# ToneControl.net
KiCad netlist of a schematic drawn in Altium Designer
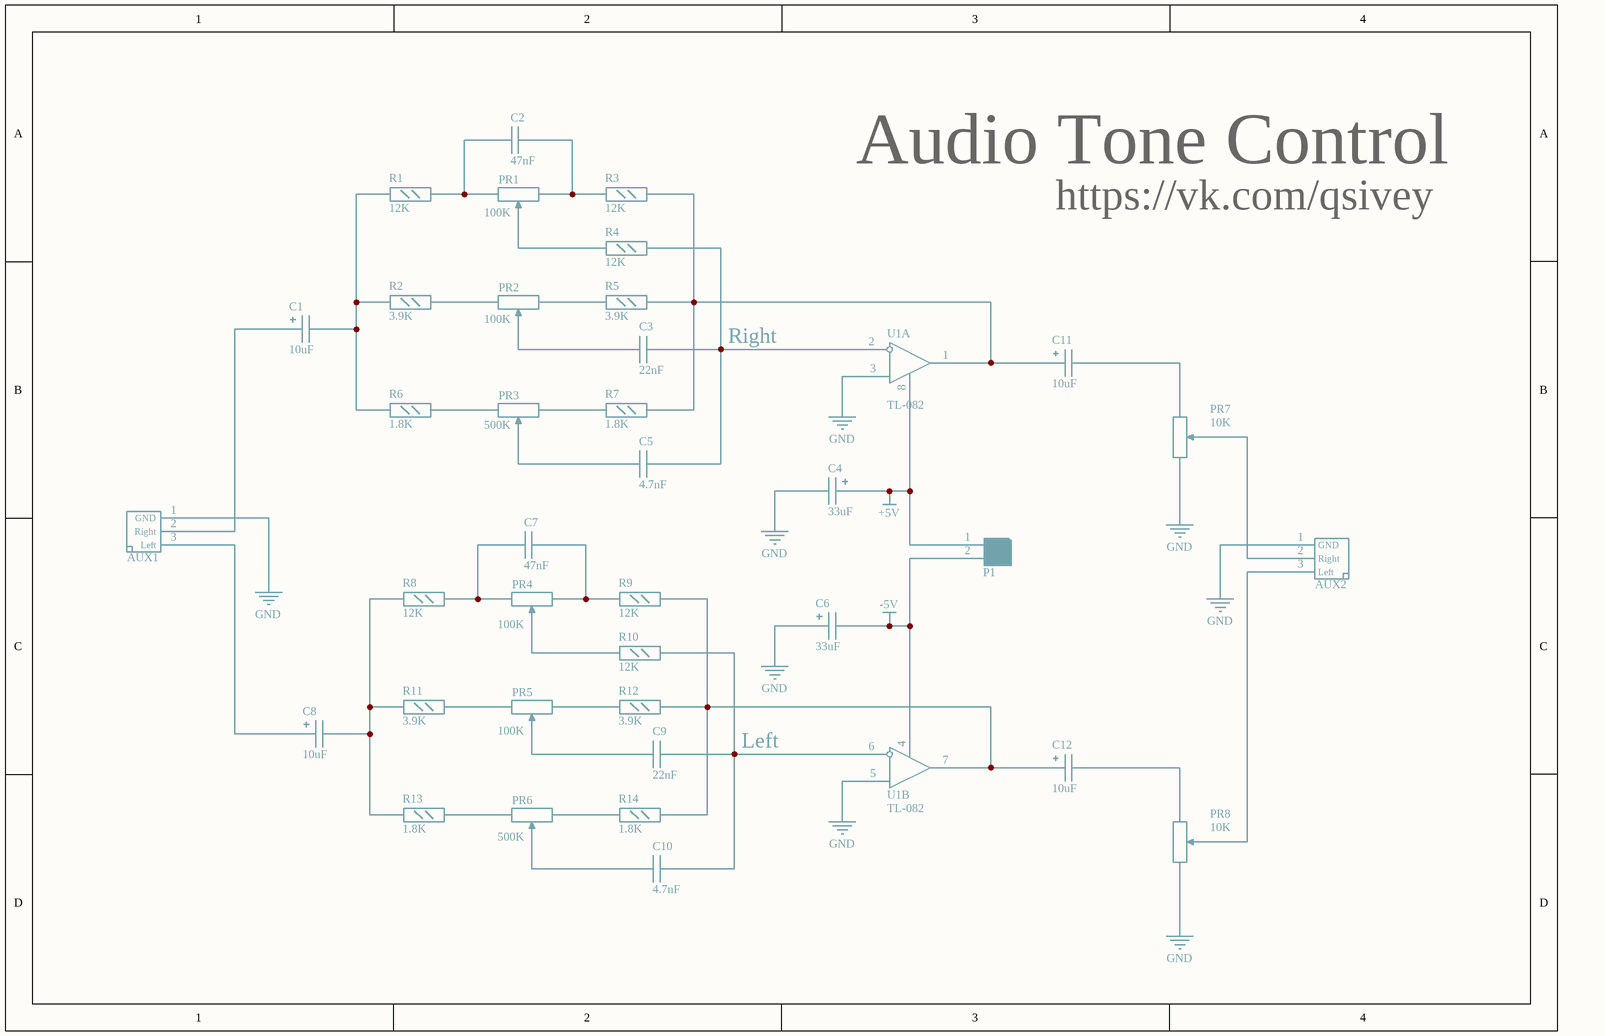
[diagram p0: ToneControl.SchDoc]

(export (version "E")
  (design (tool "Eeschema 10.0.6"))
  (components
    (comp (ref "AUX1") (value "AUX") (footprint "AUX_2") (libsource (lib "") (part "AUX_1")))
    (comp (ref "AUX2") (value "AUX") (footprint "AUX_2") (libsource (lib "CustomMillLib") (part "AUX")))
    (comp (ref "C1")
      (value "10uF")
      (footprint "CAP_POL_MED")
      (libsource (lib "CustomMillLib") (part "Cap_Pol"))
    )
    (comp (ref "C2")
      (value "47nF")
      (footprint "CAP_CER_MED")
      (libsource (lib "CustomMillLib") (part "Cap_Ceram"))
    )
    (comp (ref "C3")
      (value "22nF")
      (footprint "CAP_CER_MED")
      (libsource (lib "CustomMillLib") (part "Cap_Ceram"))
    )
    (comp (ref "C4")
      (value "33uF")
      (footprint "CAP_POL_MED")
      (libsource (lib "CustomMillLib") (part "Cap_Pol"))
    )
    (comp (ref "C5")
      (value "4.7nF")
      (footprint "CAP_CER_MED")
      (libsource (lib "CustomMillLib") (part "Cap_Ceram"))
    )
    (comp (ref "C6")
      (value "33uF")
      (footprint "CAP_POL_MED")
      (libsource (lib "CustomMillLib") (part "Cap_Pol"))
    )
    (comp (ref "C7")
      (value "47nF")
      (footprint "CAP_CER_MED")
      (libsource (lib "CustomMillLib") (part "Cap_Ceram"))
    )
    (comp (ref "C8")
      (value "10uF")
      (footprint "CAP_POL_MED")
      (libsource (lib "CustomMillLib") (part "Cap_Pol"))
    )
    (comp (ref "C9")
      (value "22nF")
      (footprint "CAP_CER_MED")
      (libsource (lib "CustomMillLib") (part "Cap_Ceram"))
    )
    (comp (ref "C10")
      (value "4.7nF")
      (footprint "CAP_CER_MED")
      (libsource (lib "CustomMillLib") (part "Cap_Ceram"))
    )
    (comp (ref "C11")
      (value "10uF")
      (footprint "CAP_POL_MED")
      (libsource (lib "CustomMillLib") (part "Cap_Pol"))
    )
    (comp (ref "C12")
      (value "10uF")
      (footprint "CAP_POL_MED")
      (libsource (lib "CustomMillLib") (part "Cap_Pol"))
    )
    (comp (ref "P1")
      (value "Header_2")
      (footprint "HEADER2")
      (libsource (lib "CustomMillLib") (part "Header_2"))
    )
    (comp (ref "PR1") (value "100K") (footprint "REOSTAT_CUS") (libsource (lib "") (part "Reostat_1")))
    (comp (ref "PR2") (value "100K") (footprint "REOSTAT_CUS") (libsource (lib "") (part "Reostat_1")))
    (comp (ref "PR3") (value "500K") (footprint "REOSTAT_CUS") (libsource (lib "") (part "Reostat_1")))
    (comp (ref "PR4") (value "100K") (footprint "REOSTAT_CUS") (libsource (lib "") (part "Reostat_1")))
    (comp (ref "PR5") (value "100K") (footprint "REOSTAT_CUS") (libsource (lib "") (part "Reostat_1")))
    (comp (ref "PR6") (value "500K") (footprint "REOSTAT_CUS") (libsource (lib "") (part "Reostat_1")))
    (comp (ref "PR7")
      (value "10K")
      (footprint "REOSTAT_CUS")
      (libsource (lib "CustomMillLib") (part "Reostat"))
    )
    (comp (ref "PR8")
      (value "10K")
      (footprint "REOSTAT_CUS")
      (libsource (lib "CustomMillLib") (part "Reostat"))
    )
    (comp (ref "R1") (value "12K") (footprint "RES_MED") (libsource (lib "CustomMillLib") (part "Res")))
    (comp (ref "R2") (value "3.9K") (footprint "RES_MED") (libsource (lib "CustomMillLib") (part "Res")))
    (comp (ref "R3") (value "12K") (footprint "RES_MED") (libsource (lib "CustomMillLib") (part "Res")))
    (comp (ref "R4") (value "12K") (footprint "RES_MED") (libsource (lib "CustomMillLib") (part "Res")))
    (comp (ref "R5") (value "3.9K") (footprint "RES_MED") (libsource (lib "CustomMillLib") (part "Res")))
    (comp (ref "R6") (value "1.8K") (footprint "RES_MED") (libsource (lib "CustomMillLib") (part "Res")))
    (comp (ref "R7") (value "1.8K") (footprint "RES_MED") (libsource (lib "CustomMillLib") (part "Res")))
    (comp (ref "R8") (value "12K") (footprint "RES_MED") (libsource (lib "CustomMillLib") (part "Res")))
    (comp (ref "R9") (value "12K") (footprint "RES_MED") (libsource (lib "CustomMillLib") (part "Res")))
    (comp (ref "R10") (value "12K") (footprint "RES_MED") (libsource (lib "CustomMillLib") (part "Res")))
    (comp (ref "R11") (value "3.9K") (footprint "RES_MED") (libsource (lib "CustomMillLib") (part "Res")))
    (comp (ref "R12") (value "3.9K") (footprint "RES_MED") (libsource (lib "CustomMillLib") (part "Res")))
    (comp (ref "R13") (value "1.8K") (footprint "RES_MED") (libsource (lib "CustomMillLib") (part "Res")))
    (comp (ref "R14") (value "1.8K") (footprint "RES_MED") (libsource (lib "CustomMillLib") (part "Res")))
    (comp (ref "U1")
      (value "TL-082")
      (footprint "PCBMillLib:DIP8")
      (libsource (lib "CustomMillLib") (part "OpAmp_8"))
    )
  )
  (nets
    (net (code "1") (name "+5V") (class "Default")
      (node (ref "C4") (pin "1") (pinfunction "61_1") (pintype "passive"))
      (node (ref "P1") (pin "1") (pinfunction "1_1") (pintype "passive"))
      (node (ref "U1") (pin "8") (pinfunction "4_8") (pintype "passive"))
    )
    (net (code "2") (name "-5V") (class "Default")
      (node (ref "C6") (pin "2") (pinfunction "62_2") (pintype "passive"))
      (node (ref "P1") (pin "2") (pinfunction "2_2") (pintype "passive"))
      (node (ref "U1") (pin "4") (pinfunction "4_4") (pintype "passive"))
    )
    (net (code "3") (name "GND") (class "Default")
      (node (ref "AUX1") (pin "1") (pinfunction "GND_1") (pintype "passive"))
      (node (ref "AUX2") (pin "1") (pinfunction "GND_1") (pintype "passive"))
      (node (ref "C4") (pin "2") (pinfunction "62_2") (pintype "passive"))
      (node (ref "C6") (pin "1") (pinfunction "61_1") (pintype "passive"))
      (node (ref "PR7") (pin "3") (pinfunction "3_3") (pintype "passive"))
      (node (ref "PR8") (pin "3") (pinfunction "3_3") (pintype "passive"))
      (node (ref "U1") (pin "3") (pinfunction "8_3") (pintype "passive"))
      (node (ref "U1") (pin "5") (pinfunction "8_5") (pintype "passive"))
    )
    (net (code "4") (name "Net-(AUX1-Left)") (class "Default")
      (node (ref "AUX1") (pin "3") (pinfunction "Left_3") (pintype "passive"))
      (node (ref "C8") (pin "1") (pinfunction "61_1") (pintype "passive"))
    )
    (net (code "5") (name "Net-(AUX1-Right)") (class "Default")
      (node (ref "AUX1") (pin "2") (pinfunction "Right_2") (pintype "passive"))
      (node (ref "C1") (pin "1") (pinfunction "61_1") (pintype "passive"))
    )
    (net (code "6") (name "Net-(AUX2-Left)") (class "Default")
      (node (ref "AUX2") (pin "3") (pinfunction "Left_3") (pintype "passive"))
      (node (ref "PR8") (pin "2") (pinfunction "2_2") (pintype "passive"))
    )
    (net (code "7") (name "Net-(AUX2-Right)") (class "Default")
      (node (ref "AUX2") (pin "2") (pinfunction "Right_2") (pintype "passive"))
      (node (ref "PR7") (pin "2") (pinfunction "2_2") (pintype "passive"))
    )
    (net (code "8") (name "Net-(C1-62)") (class "Default")
      (node (ref "C1") (pin "2") (pinfunction "62_2") (pintype "passive"))
      (node (ref "R1") (pin "1") (pinfunction "2_1") (pintype "passive"))
      (node (ref "R2") (pin "1") (pinfunction "2_1") (pintype "passive"))
      (node (ref "R6") (pin "1") (pinfunction "2_1") (pintype "passive"))
    )
    (net (code "9") (name "Net-(C2-Pad1)") (class "Default")
      (node (ref "C2") (pin "1") (pinfunction "1_1") (pintype "passive"))
      (node (ref "PR1") (pin "3") (pinfunction "3_3") (pintype "passive"))
      (node (ref "R1") (pin "2") (pinfunction "2_2") (pintype "passive"))
    )
    (net (code "10") (name "Net-(C2-Pad2)") (class "Default")
      (node (ref "C2") (pin "2") (pinfunction "2_2") (pintype "passive"))
      (node (ref "PR1") (pin "1") (pinfunction "1_1") (pintype "passive"))
      (node (ref "R3") (pin "1") (pinfunction "2_1") (pintype "passive"))
    )
    (net (code "11") (name "Net-(C3-Pad1)") (class "Default")
      (node (ref "C3") (pin "1") (pinfunction "1_1") (pintype "passive"))
      (node (ref "PR2") (pin "2") (pinfunction "2_2") (pintype "passive"))
    )
    (net (code "12") (name "Net-(C5-Pad1)") (class "Default")
      (node (ref "C5") (pin "1") (pinfunction "1_1") (pintype "passive"))
      (node (ref "PR3") (pin "2") (pinfunction "2_2") (pintype "passive"))
    )
    (net (code "13") (name "Net-(C7-Pad1)") (class "Default")
      (node (ref "C7") (pin "1") (pinfunction "1_1") (pintype "passive"))
      (node (ref "PR4") (pin "3") (pinfunction "3_3") (pintype "passive"))
      (node (ref "R8") (pin "2") (pinfunction "2_2") (pintype "passive"))
    )
    (net (code "14") (name "Net-(C7-Pad2)") (class "Default")
      (node (ref "C7") (pin "2") (pinfunction "2_2") (pintype "passive"))
      (node (ref "PR4") (pin "1") (pinfunction "1_1") (pintype "passive"))
      (node (ref "R9") (pin "1") (pinfunction "2_1") (pintype "passive"))
    )
    (net (code "15") (name "Net-(C8-62)") (class "Default")
      (node (ref "C8") (pin "2") (pinfunction "62_2") (pintype "passive"))
      (node (ref "R11") (pin "1") (pinfunction "2_1") (pintype "passive"))
      (node (ref "R13") (pin "1") (pinfunction "2_1") (pintype "passive"))
      (node (ref "R8") (pin "1") (pinfunction "2_1") (pintype "passive"))
    )
    (net (code "16") (name "Net-(C9-Pad1)") (class "Default")
      (node (ref "C9") (pin "1") (pinfunction "1_1") (pintype "passive"))
      (node (ref "PR5") (pin "2") (pinfunction "2_2") (pintype "passive"))
    )
    (net (code "17") (name "Net-(C10-Pad1)") (class "Default")
      (node (ref "C10") (pin "1") (pinfunction "1_1") (pintype "passive"))
      (node (ref "PR6") (pin "2") (pinfunction "2_2") (pintype "passive"))
    )
    (net (code "18") (name "Net-(C11-61)") (class "Default")
      (node (ref "C11") (pin "1") (pinfunction "61_1") (pintype "passive"))
      (node (ref "R3") (pin "2") (pinfunction "2_2") (pintype "passive"))
      (node (ref "R5") (pin "2") (pinfunction "2_2") (pintype "passive"))
      (node (ref "R7") (pin "2") (pinfunction "2_2") (pintype "passive"))
      (node (ref "U1") (pin "1") (pinfunction "6_1") (pintype "passive"))
    )
    (net (code "19") (name "Net-(C11-62)") (class "Default")
      (node (ref "C11") (pin "2") (pinfunction "62_2") (pintype "passive"))
      (node (ref "PR7") (pin "1") (pinfunction "1_1") (pintype "passive"))
    )
    (net (code "20") (name "Net-(C12-61)") (class "Default")
      (node (ref "C12") (pin "1") (pinfunction "61_1") (pintype "passive"))
      (node (ref "R12") (pin "2") (pinfunction "2_2") (pintype "passive"))
      (node (ref "R14") (pin "2") (pinfunction "2_2") (pintype "passive"))
      (node (ref "R9") (pin "2") (pinfunction "2_2") (pintype "passive"))
      (node (ref "U1") (pin "7") (pinfunction "6_7") (pintype "passive"))
    )
    (net (code "21") (name "Net-(C12-62)") (class "Default")
      (node (ref "C12") (pin "2") (pinfunction "62_2") (pintype "passive"))
      (node (ref "PR8") (pin "1") (pinfunction "1_1") (pintype "passive"))
    )
    (net (code "22") (name "Net-(PR1-Pad2)") (class "Default")
      (node (ref "PR1") (pin "2") (pinfunction "2_2") (pintype "passive"))
      (node (ref "R4") (pin "1") (pinfunction "2_1") (pintype "passive"))
    )
    (net (code "23") (name "Net-(PR2-Pad1)") (class "Default")
      (node (ref "PR2") (pin "1") (pinfunction "1_1") (pintype "passive"))
      (node (ref "R5") (pin "1") (pinfunction "2_1") (pintype "passive"))
    )
    (net (code "24") (name "Net-(PR2-Pad3)") (class "Default")
      (node (ref "PR2") (pin "3") (pinfunction "3_3") (pintype "passive"))
      (node (ref "R2") (pin "2") (pinfunction "2_2") (pintype "passive"))
    )
    (net (code "25") (name "Net-(PR3-Pad1)") (class "Default")
      (node (ref "PR3") (pin "1") (pinfunction "1_1") (pintype "passive"))
      (node (ref "R7") (pin "1") (pinfunction "2_1") (pintype "passive"))
    )
    (net (code "26") (name "Net-(PR3-Pad3)") (class "Default")
      (node (ref "PR3") (pin "3") (pinfunction "3_3") (pintype "passive"))
      (node (ref "R6") (pin "2") (pinfunction "2_2") (pintype "passive"))
    )
    (net (code "27") (name "Net-(PR4-Pad2)") (class "Default")
      (node (ref "PR4") (pin "2") (pinfunction "2_2") (pintype "passive"))
      (node (ref "R10") (pin "1") (pinfunction "2_1") (pintype "passive"))
    )
    (net (code "28") (name "Net-(PR5-Pad1)") (class "Default")
      (node (ref "PR5") (pin "1") (pinfunction "1_1") (pintype "passive"))
      (node (ref "R12") (pin "1") (pinfunction "2_1") (pintype "passive"))
    )
    (net (code "29") (name "Net-(PR5-Pad3)") (class "Default")
      (node (ref "PR5") (pin "3") (pinfunction "3_3") (pintype "passive"))
      (node (ref "R11") (pin "2") (pinfunction "2_2") (pintype "passive"))
    )
    (net (code "30") (name "Net-(PR6-Pad1)") (class "Default")
      (node (ref "PR6") (pin "1") (pinfunction "1_1") (pintype "passive"))
      (node (ref "R14") (pin "1") (pinfunction "2_1") (pintype "passive"))
    )
    (net (code "31") (name "Net-(PR6-Pad3)") (class "Default")
      (node (ref "PR6") (pin "3") (pinfunction "3_3") (pintype "passive"))
      (node (ref "R13") (pin "2") (pinfunction "2_2") (pintype "passive"))
    )
    (net (code "32") (name "Net-(U1A-7)") (class "Default")
      (node (ref "C3") (pin "2") (pinfunction "2_2") (pintype "passive"))
      (node (ref "C5") (pin "2") (pinfunction "2_2") (pintype "passive"))
      (node (ref "R4") (pin "2") (pinfunction "2_2") (pintype "passive"))
      (node (ref "U1") (pin "2") (pinfunction "7_2") (pintype "passive"))
    )
    (net (code "33") (name "Net-(U1B-7)") (class "Default")
      (node (ref "C10") (pin "2") (pinfunction "2_2") (pintype "passive"))
      (node (ref "C9") (pin "2") (pinfunction "2_2") (pintype "passive"))
      (node (ref "R10") (pin "2") (pinfunction "2_2") (pintype "passive"))
      (node (ref "U1") (pin "6") (pinfunction "7_6") (pintype "passive"))
    )
  )
)
